# PrNet_v04.net
KiCad netlist of a schematic drawn in Altium Designer
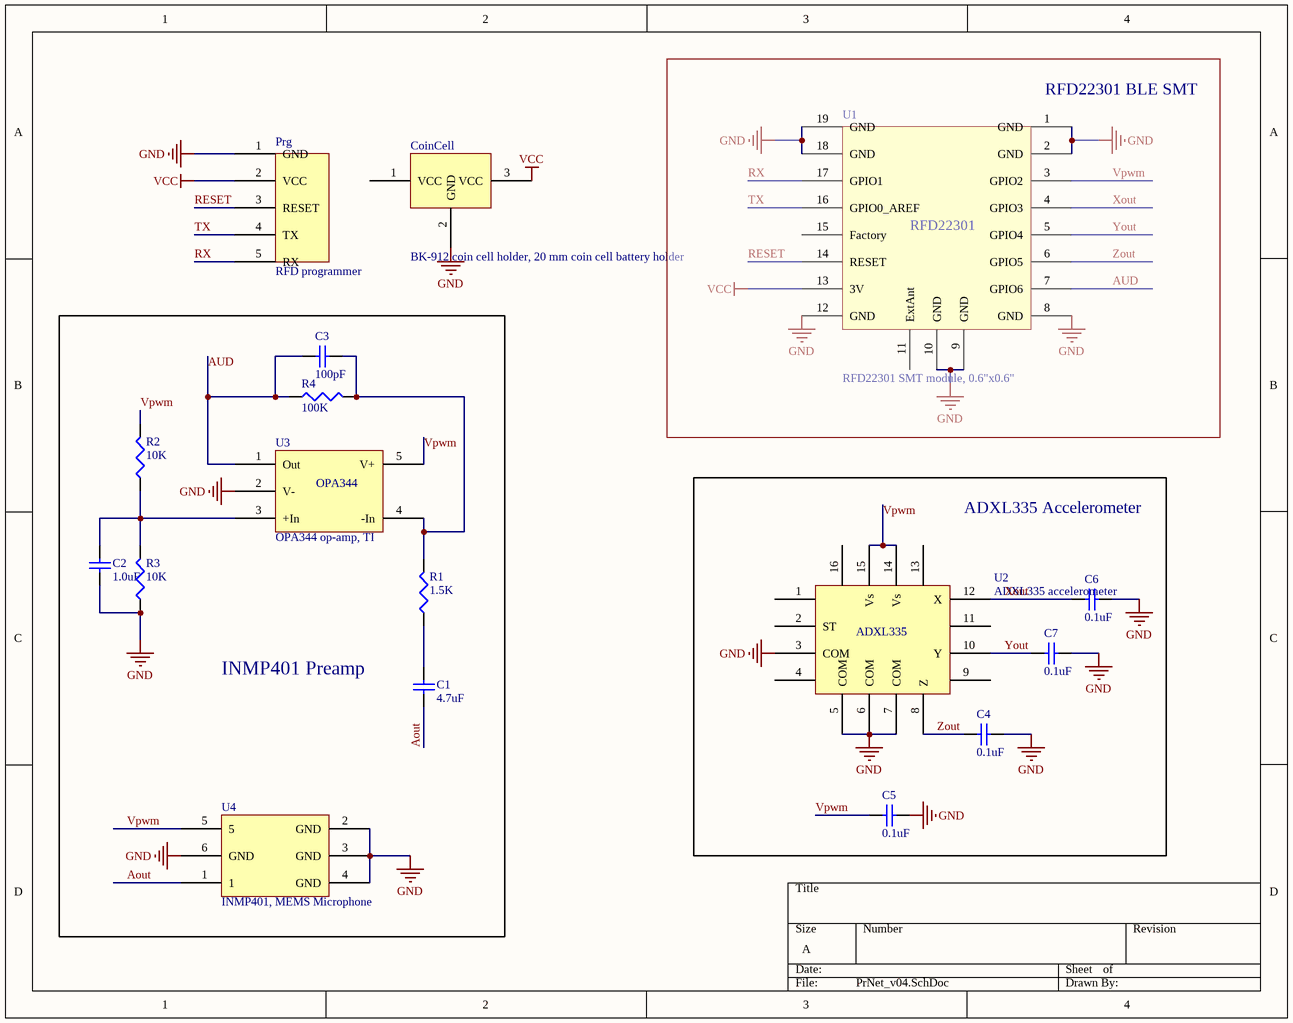
[diagram p0: PrNet_v04.SchDoc]

(export (version "E")
  (design (tool "Eeschema 10.0.6"))
  (components
    (comp (ref "C1")
      (value "4.7uF")
      (footprint "CAPC1005L")
      (description "Capacitor (Semiconductor SIM Model)")
      (fields (field (name "PUBLISHER") "Altium Limited"))
      (libsource (lib "Miscellaneous Devices") (part "Cap Semi"))
    )
    (comp (ref "C2")
      (value "1.0uF")
      (footprint "CAPC1005L")
      (description "Capacitor (Semiconductor SIM Model)")
      (fields (field (name "PUBLISHER") "Altium Limited"))
      (libsource (lib "Miscellaneous Devices") (part "Cap Semi"))
    )
    (comp (ref "C3")
      (value "100pF")
      (footprint "CAPC1005L")
      (description "Capacitor (Semiconductor SIM Model)")
      (fields (field (name "PUBLISHER") "Altium Limited"))
      (libsource (lib "Miscellaneous Devices") (part "Cap Semi"))
    )
    (comp (ref "C4")
      (value "0.1uF")
      (footprint "CAPC1005L")
      (description "Capacitor (Semiconductor SIM Model)")
      (fields (field (name "PUBLISHER") "Altium Limited"))
      (libsource (lib "Miscellaneous Devices") (part "Cap Semi"))
    )
    (comp (ref "C5")
      (value "0.1uF")
      (footprint "CAPC1005L")
      (description "Capacitor (Semiconductor SIM Model)")
      (fields (field (name "PUBLISHER") "Altium Limited"))
      (libsource (lib "Miscellaneous Devices") (part "Cap Semi"))
    )
    (comp (ref "C6")
      (value "0.1uF")
      (footprint "CAPC1005L")
      (description "Capacitor (Semiconductor SIM Model)")
      (fields (field (name "PUBLISHER") "Altium Limited"))
      (libsource (lib "Miscellaneous Devices") (part "Cap Semi"))
    )
    (comp (ref "C7")
      (value "0.1uF")
      (footprint "CAPC1005L")
      (description "Capacitor (Semiconductor SIM Model)")
      (fields (field (name "PUBLISHER") "Altium Limited"))
      (libsource (lib "Miscellaneous Devices") (part "Cap Semi"))
    )
    (comp (ref "CoinCell")
      (value "BK-912 coin cell holder, 20 mm coin cell battery holder")
      (footprint "CoinCell")
      (libsource (lib "CoinCellHolder") (part "CoinCellHolder"))
    )
    (comp (ref "Prg")
      (value "RFD programmer")
      (footprint "PrgHeader")
      (libsource (lib "ProgrammerHeader") (part "Component_1"))
    )
    (comp (ref "R1")
      (value "1.5K")
      (footprint "RESC1005L")
      (description "Resistor")
      (fields (field (name "PUBLISHER") "Altium Limited"))
      (libsource (lib "Miscellaneous Devices") (part "Res3"))
    )
    (comp (ref "R2")
      (value "10K")
      (footprint "RESC1005L")
      (description "Resistor")
      (fields (field (name "PUBLISHER") "Altium Limited"))
      (libsource (lib "Miscellaneous Devices") (part "Res3"))
    )
    (comp (ref "R3")
      (value "10K")
      (footprint "RESC1005L")
      (description "Resistor")
      (fields (field (name "PUBLISHER") "Altium Limited"))
      (libsource (lib "Miscellaneous Devices") (part "Res3"))
    )
    (comp (ref "R4")
      (value "100K")
      (footprint "RESC1005L")
      (description "Resistor")
      (fields (field (name "PUBLISHER") "Altium Limited"))
      (libsource (lib "Miscellaneous Devices") (part "Res3"))
    )
    (comp (ref "U1")
      (value "RFD22301 SMT module, 0.6\"x0.6\"")
      (footprint "RFD22301")
      (libsource (lib "RFD22301_Footprint") (part "RFD22301_Footprint"))
    )
    (comp (ref "U2")
      (value "ADXL335 accelerometer")
      (footprint "ADXL335")
      (libsource (lib "ADXL335") (part "ADXL335"))
    )
    (comp (ref "U3")
      (value "OPA344 op-amp, TI")
      (footprint "SOT23_5")
      (libsource (lib "OPA344") (part "OPA344"))
    )
    (comp (ref "U4")
      (value "INMP401, MEMS Microphone")
      (footprint "INMP401")
      (libsource (lib "INMP401") (part "INMP401"))
    )
  )
  (nets
    (net (code "1") (name "/AUD") (class "Default")
      (node (ref "C3") (pin "1") (pinfunction "1_1") (pintype "passive"))
      (node (ref "R4") (pin "1") (pinfunction "1_1") (pintype "passive"))
      (node (ref "U1") (pin "7") (pinfunction "GPIO6_7") (pintype "passive"))
      (node (ref "U3") (pin "1") (pinfunction "Out_1") (pintype "passive"))
    )
    (net (code "2") (name "/Aout") (class "Default")
      (node (ref "C1") (pin "1") (pinfunction "1_1") (pintype "passive"))
      (node (ref "U4") (pin "1") (pinfunction "1_1") (pintype "passive"))
    )
    (net (code "3") (name "/RESET") (class "Default")
      (node (ref "Prg") (pin "3") (pinfunction "RESET_3") (pintype "passive"))
      (node (ref "U1") (pin "14") (pinfunction "RESET_14") (pintype "passive"))
    )
    (net (code "4") (name "/RX") (class "Default")
      (node (ref "Prg") (pin "5") (pinfunction "RX_5") (pintype "passive"))
      (node (ref "U1") (pin "17") (pinfunction "GPIO1_17") (pintype "passive"))
    )
    (net (code "5") (name "/TX") (class "Default")
      (node (ref "Prg") (pin "4") (pinfunction "TX_4") (pintype "passive"))
      (node (ref "U1") (pin "16") (pinfunction "GPIO0_AREF_16") (pintype "passive"))
    )
    (net (code "6") (name "/Vpwm") (class "Default")
      (node (ref "C5") (pin "1") (pinfunction "1_1") (pintype "passive"))
      (node (ref "R2") (pin "2") (pinfunction "2_2") (pintype "passive"))
      (node (ref "U1") (pin "3") (pinfunction "GPIO2_3") (pintype "passive"))
      (node (ref "U2") (pin "14") (pinfunction "Vs_14") (pintype "passive"))
      (node (ref "U2") (pin "15") (pinfunction "Vs_15") (pintype "passive"))
      (node (ref "U3") (pin "5") (pinfunction "V+_5") (pintype "passive"))
      (node (ref "U4") (pin "5") (pinfunction "5_5") (pintype "passive"))
    )
    (net (code "7") (name "/Xout") (class "Default")
      (node (ref "C6") (pin "1") (pinfunction "1_1") (pintype "passive"))
      (node (ref "U1") (pin "4") (pinfunction "GPIO3_4") (pintype "passive"))
      (node (ref "U2") (pin "12") (pinfunction "X_12") (pintype "passive"))
    )
    (net (code "8") (name "/Yout") (class "Default")
      (node (ref "C7") (pin "1") (pinfunction "1_1") (pintype "passive"))
      (node (ref "U1") (pin "5") (pinfunction "GPIO4_5") (pintype "passive"))
      (node (ref "U2") (pin "10") (pinfunction "Y_10") (pintype "passive"))
    )
    (net (code "9") (name "/Zout") (class "Default")
      (node (ref "C4") (pin "1") (pinfunction "1_1") (pintype "passive"))
      (node (ref "U1") (pin "6") (pinfunction "GPIO5_6") (pintype "passive"))
      (node (ref "U2") (pin "8") (pinfunction "Z_8") (pintype "passive"))
    )
    (net (code "10") (name "GND") (class "Default")
      (node (ref "C2") (pin "1") (pinfunction "1_1") (pintype "passive"))
      (node (ref "C4") (pin "2") (pinfunction "2_2") (pintype "passive"))
      (node (ref "C5") (pin "2") (pinfunction "2_2") (pintype "passive"))
      (node (ref "C6") (pin "2") (pinfunction "2_2") (pintype "passive"))
      (node (ref "C7") (pin "2") (pinfunction "2_2") (pintype "passive"))
      (node (ref "CoinCell") (pin "2") (pinfunction "GND_2") (pintype "passive"))
      (node (ref "Prg") (pin "1") (pinfunction "GND_1") (pintype "passive"))
      (node (ref "R3") (pin "1") (pinfunction "1_1") (pintype "passive"))
      (node (ref "U1") (pin "1") (pinfunction "GND_1") (pintype "passive"))
      (node (ref "U1") (pin "10") (pinfunction "GND_10") (pintype "passive"))
      (node (ref "U1") (pin "12") (pinfunction "GND_12") (pintype "passive"))
      (node (ref "U1") (pin "18") (pinfunction "GND_18") (pintype "passive"))
      (node (ref "U1") (pin "19") (pinfunction "GND_19") (pintype "passive"))
      (node (ref "U1") (pin "2") (pinfunction "GND_2") (pintype "passive"))
      (node (ref "U1") (pin "8") (pinfunction "GND_8") (pintype "passive"))
      (node (ref "U1") (pin "9") (pinfunction "GND_9") (pintype "passive"))
      (node (ref "U2") (pin "3") (pinfunction "COM_3") (pintype "passive"))
      (node (ref "U2") (pin "5") (pinfunction "COM_5") (pintype "passive"))
      (node (ref "U2") (pin "6") (pinfunction "COM_6") (pintype "passive"))
      (node (ref "U2") (pin "7") (pinfunction "COM_7") (pintype "passive"))
      (node (ref "U3") (pin "2") (pinfunction "V-_2") (pintype "passive"))
      (node (ref "U4") (pin "2") (pinfunction "GND_2") (pintype "passive"))
      (node (ref "U4") (pin "3") (pinfunction "GND_3") (pintype "passive"))
      (node (ref "U4") (pin "4") (pinfunction "GND_4") (pintype "passive"))
      (node (ref "U4") (pin "6") (pinfunction "GND_6") (pintype "passive"))
    )
    (net (code "11") (name "Net-(C1-Pad2)") (class "Default")
      (node (ref "C1") (pin "2") (pinfunction "2_2") (pintype "passive"))
      (node (ref "R1") (pin "1") (pinfunction "1_1") (pintype "passive"))
    )
    (net (code "12") (name "Net-(U3-+In)") (class "Default")
      (node (ref "C2") (pin "2") (pinfunction "2_2") (pintype "passive"))
      (node (ref "R2") (pin "1") (pinfunction "1_1") (pintype "passive"))
      (node (ref "R3") (pin "2") (pinfunction "2_2") (pintype "passive"))
      (node (ref "U3") (pin "3") (pinfunction "+In_3") (pintype "passive"))
    )
    (net (code "13") (name "Net-(U3--In)") (class "Default")
      (node (ref "C3") (pin "2") (pinfunction "2_2") (pintype "passive"))
      (node (ref "R1") (pin "2") (pinfunction "2_2") (pintype "passive"))
      (node (ref "R4") (pin "2") (pinfunction "2_2") (pintype "passive"))
      (node (ref "U3") (pin "4") (pinfunction "-In_4") (pintype "passive"))
    )
    (net (code "14") (name "VCC") (class "Default")
      (node (ref "CoinCell") (pin "3") (pinfunction "VCC_3") (pintype "passive"))
      (node (ref "Prg") (pin "2") (pinfunction "VCC_2") (pintype "passive"))
      (node (ref "U1") (pin "13") (pinfunction "3V_13") (pintype "passive"))
    )
    (net (code "15") (name "unconnected-(CoinCell-VCC-Pad1)") (class "Default")
      (node (ref "CoinCell") (pin "1") (pinfunction "VCC_1") (pintype "passive"))
    )
    (net (code "16") (name "unconnected-(U1-ExtAnt-Pad11)") (class "Default")
      (node (ref "U1") (pin "11") (pinfunction "ExtAnt_11") (pintype "passive"))
    )
    (net (code "17") (name "unconnected-(U1-Factory-Pad15)") (class "Default")
      (node (ref "U1") (pin "15") (pinfunction "Factory_15") (pintype "passive"))
    )
    (net (code "18") (name "unconnected-(U2-Pad1)") (class "Default")
      (node (ref "U2") (pin "1") (pintype "passive"))
    )
    (net (code "19") (name "unconnected-(U2-Pad4)") (class "Default")
      (node (ref "U2") (pin "4") (pintype "passive"))
    )
    (net (code "20") (name "unconnected-(U2-Pad9)") (class "Default")
      (node (ref "U2") (pin "9") (pintype "passive"))
    )
    (net (code "21") (name "unconnected-(U2-Pad11)") (class "Default")
      (node (ref "U2") (pin "11") (pintype "passive"))
    )
    (net (code "22") (name "unconnected-(U2-Pad13)") (class "Default")
      (node (ref "U2") (pin "13") (pintype "passive"))
    )
    (net (code "23") (name "unconnected-(U2-Pad16)") (class "Default")
      (node (ref "U2") (pin "16") (pintype "passive"))
    )
    (net (code "24") (name "unconnected-(U2-ST-Pad2)") (class "Default")
      (node (ref "U2") (pin "2") (pinfunction "ST_2") (pintype "passive"))
    )
  )
)
